# Buffer_Module.net
KiCad netlist of a schematic drawn in Altium Designer
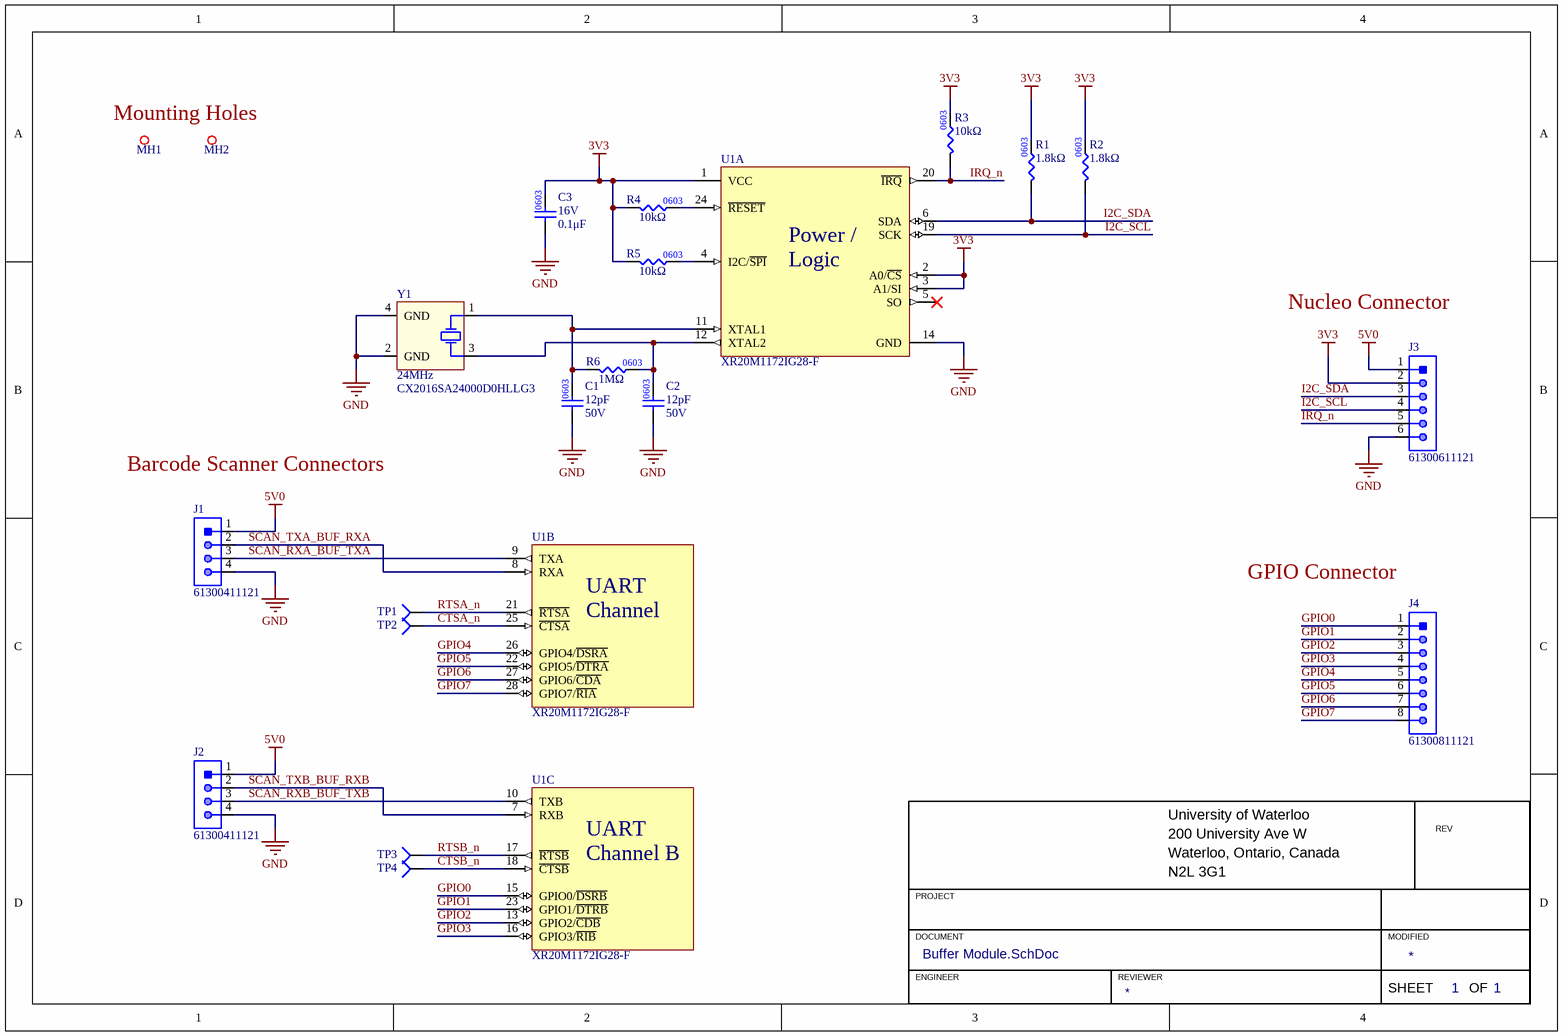
[diagram p0: Buffer Module.SchDoc]

(export (version "E")
  (design (tool "Eeschema 10.0.6"))
  (components
    (comp (ref "C1")
      (value "12pF")
      (footprint "CAP0603")
      (description "CAP CER 12PF 50V C0G/NP0 0603")
      (fields (field (name "VOLTAGE RATING") "50V") (field (name "Comment") "CAP_12pF_50V_0603"))
      (libsource (lib "Personal_Schematic_Library_2022") (part "CAP_12pF_50V_0603"))
    )
    (comp (ref "C2")
      (value "12pF")
      (footprint "CAP0603")
      (description "CAP CER 12PF 50V C0G/NP0 0603")
      (fields (field (name "VOLTAGE RATING") "50V") (field (name "Comment") "CAP_12pF_50V_0603"))
      (libsource (lib "Personal_Schematic_Library_2022") (part "CAP_12pF_50V_0603"))
    )
    (comp (ref "C3")
      (value "0.1μF")
      (footprint "CAP0603")
      (description "CAP CER 0.1UF 16V X7R 0603")
      (fields (field (name "VOLTAGE RATING") "16V") (field (name "Comment") "CAP_0.1uF_16V_0603"))
      (libsource (lib "Personal_Schematic_Library_2022") (part "CAP_0.1uF_16V_0603"))
    )
    (comp (ref "J1")
      (value "HEADER 4x1")
      (footprint "HDR1X4")
      (description "CONN HEADER VERT 4POS 2.54MM")
      (fields (field (name "MANUFACTURER PART NUMBER 1") "61300411121"))
      (libsource (lib "Personal_Schematic_Library_2022") (part "HEADER 4x1"))
    )
    (comp (ref "J2")
      (value "HEADER 4x1")
      (footprint "HDR1X4")
      (description "CONN HEADER VERT 4POS 2.54MM")
      (fields (field (name "MANUFACTURER PART NUMBER 1") "61300411121"))
      (libsource (lib "Personal_Schematic_Library_2022") (part "HEADER 4x1"))
    )
    (comp (ref "J3")
      (value "HEADER 6x1")
      (footprint "HDR1X6")
      (description "CONN HEADER VERT 6POS 2.54MM")
      (fields (field (name "MANUFACTURER PART NUMBER 1") "61300611121"))
      (libsource (lib "Personal_Schematic_Library_2022") (part "HEADER 6x1"))
    )
    (comp (ref "J4")
      (value "HEADER 8x1")
      (footprint "HDR1X8")
      (description "CONN HEADER VERT 8POS 2.54MM")
      (fields (field (name "MANUFACTURER PART NUMBER 1") "61300811121"))
      (libsource (lib "Personal_Schematic_Library_2022") (part "HEADER 8x1"))
    )
    (comp (ref "MH1")
      (value "MOUNTING_HOLE_M3")
      (footprint "MOUNTING_HOLE_3mm")
      (libsource (lib "UWRT_Schematic_Library_2020") (part "MOUNTING_HOLE_M3"))
    )
    (comp (ref "MH2")
      (value "MOUNTING_HOLE_M3")
      (footprint "MOUNTING_HOLE_3mm")
      (libsource (lib "UWRT_Schematic_Library_2020") (part "MOUNTING_HOLE_M3"))
    )
    (comp (ref "R1")
      (value "1.8kΩ")
      (footprint "RES0603")
      (description "RES 1.8K OHM 1% 1/10W 0603")
      (fields (field (name "Comment") "RES_1.8kΩ_0603_1%"))
      (libsource (lib "Personal_Schematic_Library_2022") (part "RES_1.8kΩ_0603_1%"))
    )
    (comp (ref "R2")
      (value "1.8kΩ")
      (footprint "RES0603")
      (description "RES 1.8K OHM 1% 1/10W 0603")
      (fields (field (name "Comment") "RES_1.8kΩ_0603_1%"))
      (libsource (lib "Personal_Schematic_Library_2022") (part "RES_1.8kΩ_0603_1%"))
    )
    (comp (ref "R3")
      (value "10kΩ")
      (footprint "RES0603")
      (description "RES 10K OHM 1% 1/8W 0603")
      (fields (field (name "Comment") "RES_10kΩ_0603_1%"))
      (libsource (lib "Personal_Schematic_Library_2022") (part "RES_10kΩ_0603_1%"))
    )
    (comp (ref "R4")
      (value "10kΩ")
      (footprint "RES0603")
      (description "RES 10K OHM 1% 1/8W 0603")
      (fields (field (name "Comment") "RES_10kΩ_0603_1%"))
      (libsource (lib "Personal_Schematic_Library_2022") (part "RES_10kΩ_0603_1%"))
    )
    (comp (ref "R5")
      (value "10kΩ")
      (footprint "RES0603")
      (description "RES 10K OHM 1% 1/8W 0603")
      (fields (field (name "Comment") "RES_10kΩ_0603_1%"))
      (libsource (lib "Personal_Schematic_Library_2022") (part "RES_10kΩ_0603_1%"))
    )
    (comp (ref "R6")
      (value "1MΩ")
      (footprint "RES0603")
      (description "RES 1M OHM 1% 1/10W 0603")
      (fields (field (name "Comment") "RES_1MΩ_0603_1%"))
      (libsource (lib "Personal_Schematic_Library_2022") (part "RES_1MΩ_0603_1%"))
    )
    (comp (ref "TP1")
      (value "TESTPOINT_1MM_CIRCLE")
      (footprint "TESTPOINT_CIRCLE_1MM")
      (description "TESTPOINT 1MM CIRCLE")
      (libsource (lib "Personal_Schematic_Library_2022") (part "TESTPOINT_1MM_CIRCLE"))
    )
    (comp (ref "TP2")
      (value "TESTPOINT_1MM_CIRCLE")
      (footprint "TESTPOINT_CIRCLE_1MM")
      (description "TESTPOINT 1MM CIRCLE")
      (libsource (lib "Personal_Schematic_Library_2022") (part "TESTPOINT_1MM_CIRCLE"))
    )
    (comp (ref "TP3")
      (value "TESTPOINT_1MM_CIRCLE")
      (footprint "TESTPOINT_CIRCLE_1MM")
      (description "TESTPOINT 1MM CIRCLE")
      (libsource (lib "Personal_Schematic_Library_2022") (part "TESTPOINT_1MM_CIRCLE"))
    )
    (comp (ref "TP4")
      (value "TESTPOINT_1MM_CIRCLE")
      (footprint "TESTPOINT_CIRCLE_1MM")
      (description "TESTPOINT 1MM CIRCLE")
      (libsource (lib "Personal_Schematic_Library_2022") (part "TESTPOINT_1MM_CIRCLE"))
    )
    (comp (ref "U1")
      (value "XR20M1172IG28-F")
      (footprint "MAX_28-TSSOP")
      (description "IC UART FIFO I2C/SPI 64B 28TSSOP")
      (libsource (lib "Personal_Schematic_Library_2022") (part "XR20M1172IG28-F"))
    )
    (comp (ref "Y1")
      (value "CRYSTAL_25MHZ")
      (footprint "XTAL_KYOCERA_CX2016SA")
      (description "2.0MM X 1.6MM CRYSTAL 24MHZ 8PF")
      (fields
        (field (name "FREQUENCY") "24MHz")
        (field (name "MANUFACTURER PART NUMBER 1") "CX2016SA24000D0HLLG3")
      )
      (libsource (lib "Personal_Schematic_Library_2022") (part "CRYSTAL_24MHZ_8PF"))
    )
  )
  (nets
    (net (code "1") (name "/CTSA_n") (class "Default")
      (node (ref "TP2") (pin "1") (pinfunction "=value_1") (pintype "passive"))
      (node (ref "U1") (pin "25") (pinfunction "~{CTSA}_25") (pintype "input"))
    )
    (net (code "2") (name "/CTSB_n") (class "Default")
      (node (ref "TP4") (pin "1") (pinfunction "=value_1") (pintype "passive"))
      (node (ref "U1") (pin "18") (pinfunction "~{CTSB}_18") (pintype "input"))
    )
    (net (code "3") (name "/GPIO0") (class "Default")
      (node (ref "J4") (pin "1") (pinfunction "1_1") (pintype "passive"))
      (node (ref "U1") (pin "15") (pinfunction "GPIO0/~{DSRB}_15") (pintype "bidirectional"))
    )
    (net (code "4") (name "/GPIO1") (class "Default")
      (node (ref "J4") (pin "2") (pinfunction "2_2") (pintype "passive"))
      (node (ref "U1") (pin "23") (pinfunction "GPIO1/~{DTRB}_23") (pintype "bidirectional"))
    )
    (net (code "5") (name "/GPIO2") (class "Default")
      (node (ref "J4") (pin "3") (pinfunction "3_3") (pintype "passive"))
      (node (ref "U1") (pin "13") (pinfunction "GPIO2/~{CDB}_13") (pintype "bidirectional"))
    )
    (net (code "6") (name "/GPIO3") (class "Default")
      (node (ref "J4") (pin "4") (pinfunction "4_4") (pintype "passive"))
      (node (ref "U1") (pin "16") (pinfunction "GPIO3/~{RIB}_16") (pintype "bidirectional"))
    )
    (net (code "7") (name "/GPIO4") (class "Default")
      (node (ref "J4") (pin "5") (pinfunction "5_5") (pintype "passive"))
      (node (ref "U1") (pin "26") (pinfunction "GPIO4/~{DSRA}_26") (pintype "bidirectional"))
    )
    (net (code "8") (name "/GPIO5") (class "Default")
      (node (ref "J4") (pin "6") (pinfunction "6_6") (pintype "passive"))
      (node (ref "U1") (pin "22") (pinfunction "GPIO5/~{DTRA}_22") (pintype "bidirectional"))
    )
    (net (code "9") (name "/GPIO6") (class "Default")
      (node (ref "J4") (pin "7") (pinfunction "7_7") (pintype "passive"))
      (node (ref "U1") (pin "27") (pinfunction "GPIO6/~{CDA}_27") (pintype "bidirectional"))
    )
    (net (code "10") (name "/GPIO7") (class "Default")
      (node (ref "J4") (pin "8") (pinfunction "8_8") (pintype "passive"))
      (node (ref "U1") (pin "28") (pinfunction "GPIO7/~{RIA}_28") (pintype "bidirectional"))
    )
    (net (code "11") (name "/I2C_SCL") (class "Default")
      (node (ref "J3") (pin "4") (pinfunction "4_4") (pintype "passive"))
      (node (ref "R2") (pin "1") (pinfunction "1_1") (pintype "passive"))
      (node (ref "U1") (pin "19") (pinfunction "SCK_19") (pintype "bidirectional"))
    )
    (net (code "12") (name "/I2C_SDA") (class "Default")
      (node (ref "J3") (pin "3") (pinfunction "3_3") (pintype "passive"))
      (node (ref "R1") (pin "1") (pinfunction "1_1") (pintype "passive"))
      (node (ref "U1") (pin "6") (pinfunction "SDA_6") (pintype "bidirectional"))
    )
    (net (code "13") (name "/IRQ_n") (class "Default")
      (node (ref "J3") (pin "5") (pinfunction "5_5") (pintype "passive"))
      (node (ref "R3") (pin "1") (pinfunction "1_1") (pintype "passive"))
      (node (ref "U1") (pin "20") (pinfunction "~{IRQ}_20") (pintype "output"))
    )
    (net (code "14") (name "/RTSA_n") (class "Default")
      (node (ref "TP1") (pin "1") (pinfunction "=value_1") (pintype "passive"))
      (node (ref "U1") (pin "21") (pinfunction "~{RTSA}_21") (pintype "output"))
    )
    (net (code "15") (name "/RTSB_n") (class "Default")
      (node (ref "TP3") (pin "1") (pinfunction "=value_1") (pintype "passive"))
      (node (ref "U1") (pin "17") (pinfunction "~{RTSB}_17") (pintype "output"))
    )
    (net (code "16") (name "/SCAN_RXA_BUF_TXA") (class "Default")
      (node (ref "J1") (pin "3") (pinfunction "3_3") (pintype "passive"))
      (node (ref "U1") (pin "9") (pinfunction "TXA_9") (pintype "output"))
    )
    (net (code "17") (name "/SCAN_RXB_BUF_TXB") (class "Default")
      (node (ref "J2") (pin "3") (pinfunction "3_3") (pintype "passive"))
      (node (ref "U1") (pin "10") (pinfunction "TXB_10") (pintype "output"))
    )
    (net (code "18") (name "/SCAN_TXA_BUF_RXA") (class "Default")
      (node (ref "J1") (pin "2") (pinfunction "2_2") (pintype "passive"))
      (node (ref "U1") (pin "8") (pinfunction "RXA_8") (pintype "input"))
    )
    (net (code "19") (name "/SCAN_TXB_BUF_RXB") (class "Default")
      (node (ref "J2") (pin "2") (pinfunction "2_2") (pintype "passive"))
      (node (ref "U1") (pin "7") (pinfunction "RXB_7") (pintype "input"))
    )
    (net (code "20") (name "3V3") (class "Default")
      (node (ref "C3") (pin "2") (pinfunction "2_2") (pintype "passive"))
      (node (ref "J3") (pin "2") (pinfunction "2_2") (pintype "passive"))
      (node (ref "R1") (pin "2") (pinfunction "2_2") (pintype "passive"))
      (node (ref "R2") (pin "2") (pinfunction "2_2") (pintype "passive"))
      (node (ref "R3") (pin "2") (pinfunction "2_2") (pintype "passive"))
      (node (ref "R4") (pin "1") (pinfunction "1_1") (pintype "passive"))
      (node (ref "R5") (pin "1") (pinfunction "1_1") (pintype "passive"))
      (node (ref "U1") (pin "1") (pinfunction "VCC_1") (pintype "power_in"))
      (node (ref "U1") (pin "2") (pinfunction "A0/~{CS}_2") (pintype "input"))
      (node (ref "U1") (pin "3") (pinfunction "A1/SI_3") (pintype "input"))
    )
    (net (code "21") (name "5V0") (class "Default")
      (node (ref "J1") (pin "1") (pinfunction "1_1") (pintype "passive"))
      (node (ref "J2") (pin "1") (pinfunction "1_1") (pintype "passive"))
      (node (ref "J3") (pin "1") (pinfunction "1_1") (pintype "passive"))
    )
    (net (code "22") (name "GND") (class "Default")
      (node (ref "C1") (pin "1") (pinfunction "1_1") (pintype "passive"))
      (node (ref "C2") (pin "1") (pinfunction "1_1") (pintype "passive"))
      (node (ref "C3") (pin "1") (pinfunction "1_1") (pintype "passive"))
      (node (ref "J1") (pin "4") (pinfunction "4_4") (pintype "passive"))
      (node (ref "J2") (pin "4") (pinfunction "4_4") (pintype "passive"))
      (node (ref "J3") (pin "6") (pinfunction "6_6") (pintype "passive"))
      (node (ref "U1") (pin "14") (pinfunction "GND_14") (pintype "power_in"))
      (node (ref "Y1") (pin "2") (pinfunction "GND_2") (pintype "power_in"))
      (node (ref "Y1") (pin "4") (pinfunction "GND_4") (pintype "power_in"))
    )
    (net (code "23") (name "Net-(U1A-I2C{slash}~{SPI})") (class "Default")
      (node (ref "R5") (pin "2") (pinfunction "2_2") (pintype "passive"))
      (node (ref "U1") (pin "4") (pinfunction "I2C/~{SPI}_4") (pintype "input"))
    )
    (net (code "24") (name "Net-(U1A-XTAL1)") (class "Default")
      (node (ref "C1") (pin "2") (pinfunction "2_2") (pintype "passive"))
      (node (ref "R6") (pin "1") (pinfunction "1_1") (pintype "passive"))
      (node (ref "U1") (pin "11") (pinfunction "XTAL1_11") (pintype "input"))
      (node (ref "Y1") (pin "1") (pinfunction "HOT_1") (pintype "passive"))
    )
    (net (code "25") (name "Net-(U1A-XTAL2)") (class "Default")
      (node (ref "C2") (pin "2") (pinfunction "2_2") (pintype "passive"))
      (node (ref "R6") (pin "2") (pinfunction "2_2") (pintype "passive"))
      (node (ref "U1") (pin "12") (pinfunction "XTAL2_12") (pintype "output"))
      (node (ref "Y1") (pin "3") (pinfunction "HOT_3") (pintype "passive"))
    )
    (net (code "26") (name "Net-(U1A-~{RESET})") (class "Default")
      (node (ref "R4") (pin "2") (pinfunction "2_2") (pintype "passive"))
      (node (ref "U1") (pin "24") (pinfunction "~{RESET}_24") (pintype "input"))
    )
    (net (code "27") (name "unconnected-(U1A-SO-Pad5)") (class "Default")
      (node (ref "U1") (pin "5") (pinfunction "SO_5") (pintype "output+no_connect"))
    )
  )
)
